# S3C_IOs3V3.net
KiCad netlist of a schematic drawn in Altium Designer
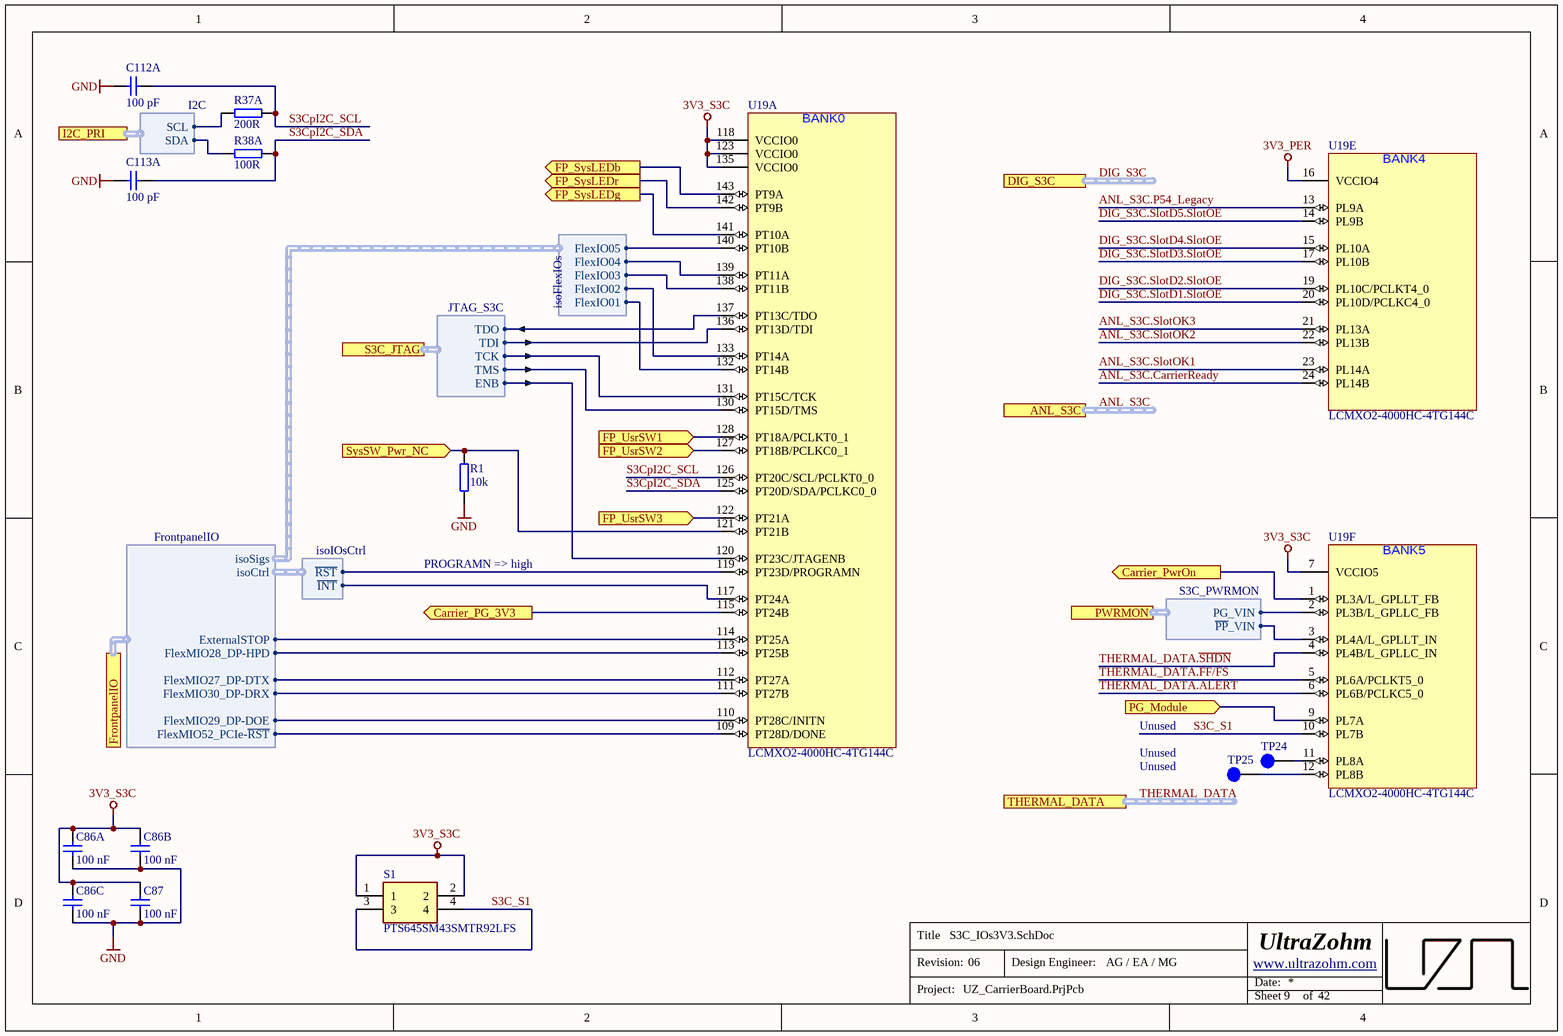
[diagram p0: S3C_IOs3V3.SchDoc]

(export (version "E")
  (design (tool "Eeschema 10.0.6"))
  (components
    (comp (ref "C86A")
      (value "100 nF")
      (footprint "C_0603_TE")
      (description "Generic capacitor")
      (fields
        (field (name "TOLERANCE") "10 %")
        (field (name "VOLTAGE") "50 V")
        (field (name "CREATED FROM") "AGeiger")
      )
      (libsource (lib "user") (part "CAP-NP"))
    )
    (comp (ref "C86B")
      (value "100 nF")
      (footprint "C_0603_TE")
      (description "Generic capacitor")
      (fields
        (field (name "TOLERANCE") "10 %")
        (field (name "VOLTAGE") "50 V")
        (field (name "CREATED FROM") "AGeiger")
      )
      (libsource (lib "user") (part "CAP-NP"))
    )
    (comp (ref "C86C")
      (value "100 nF")
      (footprint "C_0603_TE")
      (description "Generic capacitor")
      (fields
        (field (name "TOLERANCE") "10 %")
        (field (name "VOLTAGE") "50 V")
        (field (name "CREATED FROM") "AGeiger")
      )
      (libsource (lib "user") (part "CAP-NP"))
    )
    (comp (ref "C87")
      (value "100 nF")
      (footprint "C_0603_TE")
      (description "Generic capacitor")
      (fields
        (field (name "TOLERANCE") "10 %")
        (field (name "VOLTAGE") "50 V")
        (field (name "CREATED FROM") "AGeiger")
      )
      (libsource (lib "user") (part "CAP-NP"))
    )
    (comp (ref "C112A")
      (value "100 pF")
      (footprint "C_0603_TE")
      (description "Generic capacitor")
      (fields
        (field (name "MANUFACTURER PART NUMBER") "UZgen_C_0603_100pF_50V_X7R")
        (field (name "MANUFACTURER") "UZgen")
        (field (name "CREATED FROM") "UZgenTool")
      )
      (libsource (lib "user") (part "CAP-NP"))
    )
    (comp (ref "C113A")
      (value "100 pF")
      (footprint "C_0603_TE")
      (description "Generic capacitor")
      (fields
        (field (name "MANUFACTURER PART NUMBER") "UZgen_C_0603_100pF_50V_X7R")
        (field (name "MANUFACTURER") "UZgen")
        (field (name "CREATED FROM") "UZgenTool")
      )
      (libsource (lib "user") (part "CAP-NP"))
    )
    (comp (ref "R1")
      (value "10k")
      (footprint "R_0603_TE")
      (description "Generic resistor")
      (fields
        (field (name "MANUFACTURER PART NUMBER") "UZgen_R_0603_10k")
        (field (name "MANUFACTURER") "UZgen")
        (field (name "CREATED FROM") "AGeiger")
      )
      (libsource (lib "user") (part "RES"))
    )
    (comp (ref "R37A")
      (value "200R")
      (footprint "R_0603_TE")
      (description "Generic resistor")
      (fields
        (field (name "MANUFACTURER PART NUMBER") "UZgen_R_0603_200R")
        (field (name "MANUFACTURER") "UZgen")
        (field (name "CREATED FROM") "UZgenTool")
      )
      (libsource (lib "user") (part "RES"))
    )
    (comp (ref "R38A")
      (value "100R")
      (footprint "R_0603_TE")
      (description "Generic resistor")
      (fields
        (field (name "MANUFACTURER PART NUMBER") "UZgen_R_0603_100R")
        (field (name "MANUFACTURER") "UZgen")
        (field (name "CREATED FROM") "UZgenTool")
      )
      (libsource (lib "user") (part "RES"))
    )
    (comp (ref "S1")
      (value "PTS645SM43SMTR92LFS")
      (footprint "PTS645_SMT")
      (description "50mA SPST 160gf 12V SMD-4P,6x6mm Tactile Switches ROHS")
      (fields
        (field (name "MOUSER PART NUMBER") "611-PTS645SM43SMTR92")
        (field (name "MANUFACTURER") "C&K COMPONENTS")
        (field (name "CREATED FROM") "AGeiger")
      )
      (libsource (lib "user") (part "PTS645SM43SMTR92LFS"))
    )
    (comp (ref "TP24")
      (value "Testpoint 1mm")
      (footprint "TP_1mm")
      (fields
        (field (name "MANUFACTURER PART NUMBER") "NULL")
        (field (name "CREATED") "2018_06_25_AGeiger")
        (field (name "CREATED FROM") "AGeiger")
      )
      (libsource (lib "user") (part "TP_1mm"))
    )
    (comp (ref "TP25")
      (value "Testpoint 1mm")
      (footprint "TP_1mm")
      (fields
        (field (name "MANUFACTURER PART NUMBER") "NULL")
        (field (name "CREATED") "2018_06_25_AGeiger")
        (field (name "CREATED FROM") "AGeiger")
      )
      (libsource (lib "user") (part "TP_1mm"))
    )
    (comp (ref "U19")
      (value "LCMXO2-4000HC-4TG144C")
      (footprint "QFP50P2200X2200X160-144N")
      (description "TQFP-144(20x20) Programmable Logic Device (CPLDs/FPGAs) ROHS")
      (fields
        (field (name "MANUFACTURER") "Lattice")
        (field (name "LCSC PART NUMBER") "C1521625")
        (field (name "CREATED FROM") "FRosner")
      )
      (libsource (lib "user") (part "LCMXO2-4000"))
    )
  )
  (nets
    (net (code "10") (name "/ANL_S3C.CarrierReady") (class "Default")
      (node (ref "U19") (pin "24") (pinfunction "PL14B_24") (pintype "bidirectional"))
    )
    (net (code "11") (name "/ANL_S3C.P54_Legacy") (class "Default")
      (node (ref "U19") (pin "13") (pinfunction "PL9A_13") (pintype "bidirectional"))
    )
    (net (code "12") (name "/ANL_S3C.SlotOK1") (class "Default")
      (node (ref "U19") (pin "23") (pinfunction "PL14A_23") (pintype "bidirectional"))
    )
    (net (code "13") (name "/ANL_S3C.SlotOK2") (class "Default")
      (node (ref "U19") (pin "22") (pinfunction "PL13B_22") (pintype "bidirectional"))
    )
    (net (code "14") (name "/ANL_S3C.SlotOK3") (class "Default")
      (node (ref "U19") (pin "21") (pinfunction "PL13A_21") (pintype "bidirectional"))
    )
    (net (code "15") (name "/Carrier_PG_3V3") (class "Default")
      (node (ref "U19") (pin "115") (pinfunction "PT24B_115") (pintype "bidirectional"))
    )
    (net (code "16") (name "/Carrier_PwrOn") (class "Default")
      (node (ref "U19") (pin "1") (pinfunction "PL3A/L_GPLLT_FB_1") (pintype "bidirectional"))
    )
    (net (code "17") (name "/DIG_S3C.SlotD1.SlotOE") (class "Default")
      (node (ref "U19") (pin "20") (pinfunction "PL10D/PCLKC4_0_20") (pintype "bidirectional"))
    )
    (net (code "18") (name "/DIG_S3C.SlotD2.SlotOE") (class "Default")
      (node (ref "U19") (pin "19") (pinfunction "PL10C/PCLKT4_0_19") (pintype "bidirectional"))
    )
    (net (code "19") (name "/DIG_S3C.SlotD3.SlotOE") (class "Default")
      (node (ref "U19") (pin "17") (pinfunction "PL10B_17") (pintype "bidirectional"))
    )
    (net (code "20") (name "/DIG_S3C.SlotD4.SlotOE") (class "Default")
      (node (ref "U19") (pin "15") (pinfunction "PL10A_15") (pintype "bidirectional"))
    )
    (net (code "21") (name "/DIG_S3C.SlotD5.SlotOE") (class "Default")
      (node (ref "U19") (pin "14") (pinfunction "PL9B_14") (pintype "bidirectional"))
    )
    (net (code "22") (name "/ENB") (class "Default")
      (node (ref "U19") (pin "120") (pinfunction "PT23C/JTAGENB_120") (pintype "bidirectional"))
    )
    (net (code "23") (name "/ExternalSTOP") (class "Default")
      (node (ref "U19") (pin "114") (pinfunction "PT25A_114") (pintype "bidirectional"))
    )
    (net (code "24") (name "/FP_SysLEDb") (class "Default")
      (node (ref "U19") (pin "143") (pinfunction "PT9A_143") (pintype "bidirectional"))
    )
    (net (code "25") (name "/FP_SysLEDg") (class "Default")
      (node (ref "U19") (pin "141") (pinfunction "PT10A_141") (pintype "bidirectional"))
    )
    (net (code "26") (name "/FP_SysLEDr") (class "Default")
      (node (ref "U19") (pin "142") (pinfunction "PT9B_142") (pintype "bidirectional"))
    )
    (net (code "27") (name "/FP_UsrSW1") (class "Default")
      (node (ref "U19") (pin "128") (pinfunction "PT18A/PCLKT0_1_128") (pintype "bidirectional"))
    )
    (net (code "28") (name "/FP_UsrSW2") (class "Default")
      (node (ref "U19") (pin "127") (pinfunction "PT18B/PCLKC0_1_127") (pintype "bidirectional"))
    )
    (net (code "29") (name "/FP_UsrSW3") (class "Default")
      (node (ref "U19") (pin "122") (pinfunction "PT21A_122") (pintype "bidirectional"))
    )
    (net (code "30") (name "/FlexIO01") (class "Default")
      (node (ref "U19") (pin "132") (pinfunction "PT14B_132") (pintype "bidirectional"))
    )
    (net (code "31") (name "/FlexIO02") (class "Default")
      (node (ref "U19") (pin "133") (pinfunction "PT14A_133") (pintype "bidirectional"))
    )
    (net (code "32") (name "/FlexIO03") (class "Default")
      (node (ref "U19") (pin "138") (pinfunction "PT11B_138") (pintype "bidirectional"))
    )
    (net (code "33") (name "/FlexIO04") (class "Default")
      (node (ref "U19") (pin "139") (pinfunction "PT11A_139") (pintype "bidirectional"))
    )
    (net (code "34") (name "/FlexIO05") (class "Default")
      (node (ref "U19") (pin "140") (pinfunction "PT10B_140") (pintype "bidirectional"))
    )
    (net (code "35") (name "/PG_Module") (class "Default")
      (node (ref "U19") (pin "9") (pinfunction "PL7A_9") (pintype "bidirectional"))
    )
    (net (code "36") (name "/PG_VIN") (class "Default")
      (node (ref "U19") (pin "2") (pinfunction "PL3B/L_GPLLC_FB_2") (pintype "bidirectional"))
    )
    (net (code "37") (name "/S3C_S1") (class "Default")
      (node (ref "S1") (pin "3") (pinfunction "3_3") (pintype "passive"))
      (node (ref "S1") (pin "4") (pinfunction "4_4") (pintype "passive"))
      (node (ref "U19") (pin "10") (pinfunction "PL7B_10") (pintype "bidirectional"))
    )
    (net (code "38") (name "/S3CpI2C_SCL") (class "Default")
      (node (ref "C112A") (pin "1") (pinfunction "1_1") (pintype "passive"))
      (node (ref "R37A") (pin "2") (pinfunction "2_2") (pintype "passive"))
      (node (ref "U19") (pin "126") (pinfunction "PT20C/SCL/PCLKT0_0_126") (pintype "bidirectional"))
    )
    (net (code "39") (name "/S3CpI2C_SDA") (class "Default")
      (node (ref "C113A") (pin "1") (pinfunction "1_1") (pintype "passive"))
      (node (ref "R38A") (pin "2") (pinfunction "2_2") (pintype "passive"))
      (node (ref "U19") (pin "125") (pinfunction "PT20D/SDA/PCLKC0_0_125") (pintype "bidirectional"))
    )
    (net (code "40") (name "/SCL") (class "Default")
      (node (ref "R37A") (pin "1") (pinfunction "1_1") (pintype "passive"))
    )
    (net (code "41") (name "/SDA") (class "Default")
      (node (ref "R38A") (pin "1") (pinfunction "1_1") (pintype "passive"))
    )
    (net (code "42") (name "/SysSW_Pwr_NC") (class "Default")
      (node (ref "R1") (pin "2") (pinfunction "2_2") (pintype "passive"))
      (node (ref "U19") (pin "121") (pinfunction "PT21B_121") (pintype "bidirectional"))
    )
    (net (code "43") (name "/TCK") (class "Default")
      (node (ref "U19") (pin "131") (pinfunction "PT15C/TCK_131") (pintype "bidirectional"))
    )
    (net (code "44") (name "/TDI") (class "Default")
      (node (ref "U19") (pin "136") (pinfunction "PT13D/TDI_136") (pintype "bidirectional"))
    )
    (net (code "45") (name "/TDO") (class "Default")
      (node (ref "U19") (pin "137") (pinfunction "PT13C/TDO_137") (pintype "bidirectional"))
    )
    (net (code "46") (name "/THERMAL_DATA.~{ALERT}") (class "Default")
      (node (ref "U19") (pin "6") (pinfunction "PL6B/PCLKC5_0_6") (pintype "bidirectional"))
    )
    (net (code "47") (name "/THERMAL_DATA.~{FF{slash}FS}") (class "Default")
      (node (ref "U19") (pin "5") (pinfunction "PL6A/PCLKT5_0_5") (pintype "bidirectional"))
    )
    (net (code "48") (name "/THERMAL_DATA.~{SHDN}") (class "Default")
      (node (ref "U19") (pin "4") (pinfunction "PL4B/L_GPLLC_IN_4") (pintype "bidirectional"))
    )
    (net (code "49") (name "/TMS") (class "Default")
      (node (ref "U19") (pin "130") (pinfunction "PT15D/TMS_130") (pintype "bidirectional"))
    )
    (net (code "59") (name "/~{INT}") (class "Default")
      (node (ref "U19") (pin "117") (pinfunction "PT24A_117") (pintype "bidirectional"))
    )
    (net (code "60") (name "/~{PP}_VIN") (class "Default")
      (node (ref "U19") (pin "3") (pinfunction "PL4A/L_GPLLT_IN_3") (pintype "bidirectional"))
    )
    (net (code "61") (name "/~{RST}") (class "Default")
      (node (ref "U19") (pin "119") (pinfunction "PT23D/PROGRAMN_119") (pintype "bidirectional"))
    )
    (net (code "62") (name "3V3_PER") (class "Default")
      (node (ref "U19") (pin "16") (pinfunction "VCCIO4_16") (pintype "power_in"))
    )
    (net (code "63") (name "3V3_S3C") (class "Default")
      (node (ref "C86A") (pin "2") (pinfunction "2_2") (pintype "passive"))
      (node (ref "C86B") (pin "2") (pinfunction "2_2") (pintype "passive"))
      (node (ref "C86C") (pin "2") (pinfunction "2_2") (pintype "passive"))
      (node (ref "C87") (pin "2") (pinfunction "2_2") (pintype "passive"))
      (node (ref "S1") (pin "1") (pinfunction "1_1") (pintype "passive"))
      (node (ref "S1") (pin "2") (pinfunction "2_2") (pintype "passive"))
      (node (ref "U19") (pin "118") (pinfunction "VCCIO0_118") (pintype "power_in"))
      (node (ref "U19") (pin "123") (pinfunction "VCCIO0_123") (pintype "power_in"))
      (node (ref "U19") (pin "135") (pinfunction "VCCIO0_135") (pintype "power_in"))
      (node (ref "U19") (pin "7") (pinfunction "VCCIO5_7") (pintype "power_in"))
    )
    (net (code "64") (name "GND") (class "Default")
      (node (ref "C112A") (pin "2") (pinfunction "2_2") (pintype "passive"))
      (node (ref "C113A") (pin "2") (pinfunction "2_2") (pintype "passive"))
      (node (ref "C86A") (pin "1") (pinfunction "1_1") (pintype "passive"))
      (node (ref "C86B") (pin "1") (pinfunction "1_1") (pintype "passive"))
      (node (ref "C86C") (pin "1") (pinfunction "1_1") (pintype "passive"))
      (node (ref "C87") (pin "1") (pinfunction "1_1") (pintype "passive"))
      (node (ref "R1") (pin "1") (pinfunction "1_1") (pintype "passive"))
    )
    (net (code "65") (name "Net-(U19F-PL8A)") (class "Default")
      (node (ref "TP24") (pin "1") (pintype "passive"))
      (node (ref "U19") (pin "11") (pinfunction "PL8A_11") (pintype "bidirectional"))
    )
    (net (code "66") (name "Net-(U19F-PL8B)") (class "Default")
      (node (ref "TP25") (pin "1") (pintype "passive"))
      (node (ref "U19") (pin "12") (pinfunction "PL8B_12") (pintype "bidirectional"))
    )
    (net (code "67") (name "unconnected-(U19A-PT25B-Pad113)") (class "Default")
      (node (ref "U19") (pin "113") (pinfunction "PT25B_113") (pintype "bidirectional"))
    )
    (net (code "68") (name "unconnected-(U19A-PT27A-Pad112)") (class "Default")
      (node (ref "U19") (pin "112") (pinfunction "PT27A_112") (pintype "bidirectional"))
    )
    (net (code "69") (name "unconnected-(U19A-PT27B-Pad111)") (class "Default")
      (node (ref "U19") (pin "111") (pinfunction "PT27B_111") (pintype "bidirectional"))
    )
    (net (code "70") (name "unconnected-(U19A-PT28C{slash}INITN-Pad110)") (class "Default")
      (node (ref "U19") (pin "110") (pinfunction "PT28C/INITN_110") (pintype "bidirectional"))
    )
    (net (code "71") (name "unconnected-(U19A-PT28D{slash}DONE-Pad109)") (class "Default")
      (node (ref "U19") (pin "109") (pinfunction "PT28D/DONE_109") (pintype "bidirectional"))
    )
  )
)
